# Dual_linear_VCA_chip.net
KiCad netlist of a schematic drawn in EAGLE
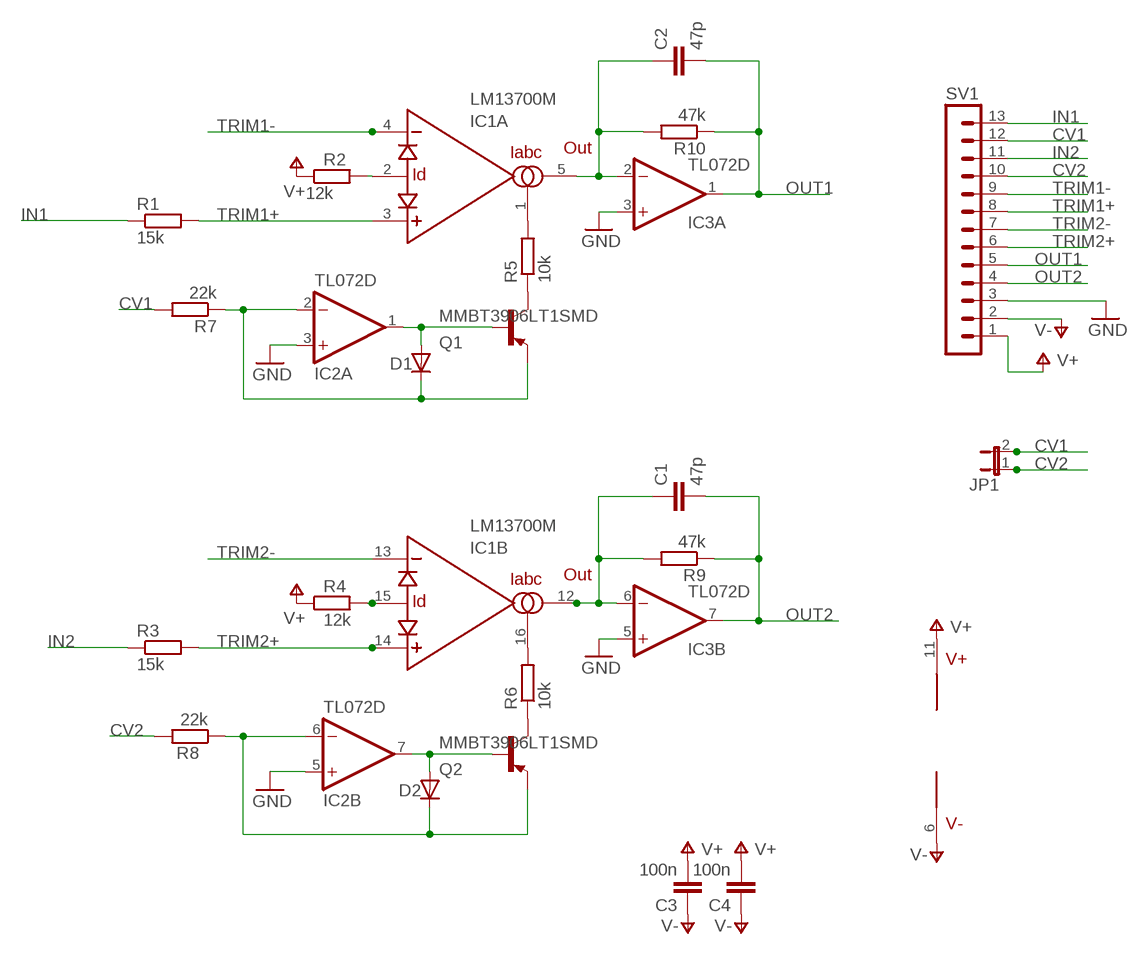
[diagram p0: schematic, sheet 1]

(export (version "E")
  (design (tool "Eeschema 10.0.6"))
  (components
    (comp (ref "C1")
      (value "47p")
      (footprint "eagle-import:C0805")
      (libsource (lib "eagle-import") (part "C-EUC0805"))
    )
    (comp (ref "C2")
      (value "47p")
      (footprint "eagle-import:C0805")
      (libsource (lib "eagle-import") (part "C-EUC0805"))
    )
    (comp (ref "C3")
      (value "100n")
      (footprint "eagle-import:C0805")
      (libsource (lib "eagle-import") (part "C-EUC0805"))
    )
    (comp (ref "C4")
      (value "100n")
      (footprint "eagle-import:C0805")
      (libsource (lib "eagle-import") (part "C-EUC0805"))
    )
    (comp (ref "D1")
      (value "DIODE-SOD80C")
      (footprint "eagle-import:SOD80C")
      (libsource (lib "eagle-import") (part "DIODE-SOD80C"))
    )
    (comp (ref "D2")
      (value "DIODE-SOD80C")
      (footprint "eagle-import:SOD80C")
      (libsource (lib "eagle-import") (part "DIODE-SOD80C"))
    )
    (comp (ref "IC1")
      (value "LM13700M")
      (footprint "eagle-import:SO16")
      (libsource (lib "eagle-import") (part "LM13700M"))
    )
    (comp (ref "IC2")
      (value "TL072D")
      (footprint "eagle-import:SO08")
      (libsource (lib "eagle-import") (part "TL072D"))
    )
    (comp (ref "IC3")
      (value "TL072D")
      (footprint "eagle-import:SO08")
      (libsource (lib "eagle-import") (part "TL072D"))
    )
    (comp (ref "JP1")
      (value "JP1E")
      (footprint "eagle-import:JP1")
      (libsource (lib "eagle-import") (part "JP1E"))
    )
    (comp (ref "Q1")
      (value "MMBT3906LT1SMD")
      (footprint "eagle-import:SOT23-BEC")
      (libsource (lib "eagle-import") (part "MMBT3906SMDLT1"))
    )
    (comp (ref "Q2")
      (value "MMBT3906LT1SMD")
      (footprint "eagle-import:SOT23-BEC")
      (libsource (lib "eagle-import") (part "MMBT3906SMDLT1"))
    )
    (comp (ref "R1")
      (value "15k")
      (footprint "eagle-import:R0805")
      (libsource (lib "eagle-import") (part "R-EU_R0805"))
    )
    (comp (ref "R2")
      (value "12k")
      (footprint "eagle-import:R0805")
      (libsource (lib "eagle-import") (part "R-EU_R0805"))
    )
    (comp (ref "R3")
      (value "15k")
      (footprint "eagle-import:R0805")
      (libsource (lib "eagle-import") (part "R-EU_R0805"))
    )
    (comp (ref "R4")
      (value "12k")
      (footprint "eagle-import:R0805")
      (libsource (lib "eagle-import") (part "R-EU_R0805"))
    )
    (comp (ref "R5")
      (value "10k")
      (footprint "eagle-import:R0805")
      (libsource (lib "eagle-import") (part "R-EU_R0805"))
    )
    (comp (ref "R6")
      (value "10k")
      (footprint "eagle-import:R0805")
      (libsource (lib "eagle-import") (part "R-EU_R0805"))
    )
    (comp (ref "R7")
      (value "22k")
      (footprint "eagle-import:R0805")
      (libsource (lib "eagle-import") (part "R-EU_R0805"))
    )
    (comp (ref "R8")
      (value "22k")
      (footprint "eagle-import:R0805")
      (libsource (lib "eagle-import") (part "R-EU_R0805"))
    )
    (comp (ref "R9")
      (value "47k")
      (footprint "eagle-import:R0805")
      (libsource (lib "eagle-import") (part "R-EU_R0805"))
    )
    (comp (ref "R10")
      (value "47k")
      (footprint "eagle-import:R0805")
      (libsource (lib "eagle-import") (part "R-EU_R0805"))
    )
    (comp (ref "SV1")
      (value "MA13-1")
      (footprint "eagle-import:MA13-1")
      (libsource (lib "eagle-import") (part "MA13-1"))
    )
  )
  (nets
    (net (code "1") (name "/CV1") (class "Default")
      (node (ref "JP1") (pin "2") (pinfunction "2_2") (pintype "passive"))
      (node (ref "R7") (pin "2") (pinfunction "2_2") (pintype "passive"))
      (node (ref "SV1") (pin "12") (pinfunction "12_12") (pintype "passive"))
    )
    (net (code "2") (name "/CV2") (class "Default")
      (node (ref "JP1") (pin "1") (pinfunction "1_1") (pintype "passive"))
      (node (ref "R8") (pin "2") (pinfunction "2_2") (pintype "passive"))
      (node (ref "SV1") (pin "10") (pinfunction "10_10") (pintype "passive"))
    )
    (net (code "3") (name "/IN1") (class "Default")
      (node (ref "R1") (pin "1") (pinfunction "1_1") (pintype "passive"))
      (node (ref "SV1") (pin "13") (pinfunction "13_13") (pintype "passive"))
    )
    (net (code "4") (name "/IN2") (class "Default")
      (node (ref "R3") (pin "1") (pinfunction "1_1") (pintype "passive"))
      (node (ref "SV1") (pin "11") (pinfunction "11_11") (pintype "passive"))
    )
    (net (code "5") (name "/OUT1") (class "Default")
      (node (ref "C2") (pin "2") (pinfunction "2_2") (pintype "passive"))
      (node (ref "IC3") (pin "1") (pinfunction "OUT_1") (pintype "output"))
      (node (ref "R10") (pin "1") (pinfunction "1_1") (pintype "passive"))
      (node (ref "SV1") (pin "4") (pinfunction "4_4") (pintype "passive"))
    )
    (net (code "6") (name "/OUT2") (class "Default")
      (node (ref "C1") (pin "2") (pinfunction "2_2") (pintype "passive"))
      (node (ref "IC3") (pin "7") (pinfunction "OUT_7") (pintype "output"))
      (node (ref "R9") (pin "1") (pinfunction "1_1") (pintype "passive"))
      (node (ref "SV1") (pin "5") (pinfunction "5_5") (pintype "passive"))
    )
    (net (code "7") (name "/TRIM1+") (class "Default")
      (node (ref "IC1") (pin "3") (pinfunction "+IN_3") (pintype "bidirectional"))
      (node (ref "R1") (pin "2") (pinfunction "2_2") (pintype "passive"))
      (node (ref "SV1") (pin "8") (pinfunction "8_8") (pintype "passive"))
    )
    (net (code "8") (name "/TRIM1-") (class "Default")
      (node (ref "IC1") (pin "4") (pinfunction "-IN_4") (pintype "bidirectional"))
      (node (ref "SV1") (pin "9") (pinfunction "9_9") (pintype "passive"))
    )
    (net (code "9") (name "/TRIM2+") (class "Default")
      (node (ref "IC1") (pin "14") (pinfunction "+IN_14") (pintype "bidirectional"))
      (node (ref "R3") (pin "2") (pinfunction "2_2") (pintype "passive"))
      (node (ref "SV1") (pin "6") (pinfunction "6_6") (pintype "passive"))
    )
    (net (code "10") (name "/TRIM2-") (class "Default")
      (node (ref "IC1") (pin "13") (pinfunction "-IN_13") (pintype "bidirectional"))
      (node (ref "SV1") (pin "7") (pinfunction "7_7") (pintype "passive"))
    )
    (net (code "11") (name "GND") (class "Default")
      (node (ref "IC2") (pin "3") (pinfunction "+IN_3") (pintype "input"))
      (node (ref "IC2") (pin "5") (pinfunction "+IN_5") (pintype "input"))
      (node (ref "IC3") (pin "3") (pinfunction "+IN_3") (pintype "input"))
      (node (ref "IC3") (pin "5") (pinfunction "+IN_5") (pintype "input"))
      (node (ref "SV1") (pin "3") (pinfunction "3_3") (pintype "passive"))
    )
    (net (code "12") (name "Net-(IC1A-IABC)") (class "Default")
      (node (ref "IC1") (pin "1") (pinfunction "IABC_1") (pintype "bidirectional"))
      (node (ref "R5") (pin "2") (pinfunction "2_2") (pintype "passive"))
    )
    (net (code "13") (name "Net-(IC1A-ID)") (class "Default")
      (node (ref "IC1") (pin "2") (pinfunction "ID_2") (pintype "bidirectional"))
      (node (ref "R2") (pin "2") (pinfunction "2_2") (pintype "passive"))
    )
    (net (code "14") (name "Net-(IC1A-OUT)") (class "Default")
      (node (ref "C2") (pin "1") (pinfunction "1_1") (pintype "passive"))
      (node (ref "IC1") (pin "5") (pinfunction "OUT_5") (pintype "bidirectional"))
      (node (ref "IC3") (pin "2") (pinfunction "-IN_2") (pintype "input"))
      (node (ref "R10") (pin "2") (pinfunction "2_2") (pintype "passive"))
    )
    (net (code "15") (name "Net-(IC1B-IABC)") (class "Default")
      (node (ref "IC1") (pin "16") (pinfunction "IABC_16") (pintype "bidirectional"))
      (node (ref "R6") (pin "2") (pinfunction "2_2") (pintype "passive"))
    )
    (net (code "16") (name "Net-(IC1B-ID)") (class "Default")
      (node (ref "IC1") (pin "15") (pinfunction "ID_15") (pintype "bidirectional"))
      (node (ref "R4") (pin "2") (pinfunction "2_2") (pintype "passive"))
    )
    (net (code "17") (name "Net-(IC1B-OUT)") (class "Default")
      (node (ref "C1") (pin "1") (pinfunction "1_1") (pintype "passive"))
      (node (ref "IC1") (pin "12") (pinfunction "OUT_12") (pintype "bidirectional"))
      (node (ref "IC3") (pin "6") (pinfunction "-IN_6") (pintype "input"))
      (node (ref "R9") (pin "2") (pinfunction "2_2") (pintype "passive"))
    )
    (net (code "18") (name "Net-(IC2A--IN)") (class "Default")
      (node (ref "D1") (pin "C") (pinfunction "C_C") (pintype "passive"))
      (node (ref "IC2") (pin "2") (pinfunction "-IN_2") (pintype "input"))
      (node (ref "Q1") (pin "E") (pinfunction "E_E") (pintype "passive"))
      (node (ref "R7") (pin "1") (pinfunction "1_1") (pintype "passive"))
    )
    (net (code "19") (name "Net-(IC2A-OUT)") (class "Default")
      (node (ref "D1") (pin "A") (pinfunction "A_A") (pintype "passive"))
      (node (ref "IC2") (pin "1") (pinfunction "OUT_1") (pintype "output"))
      (node (ref "Q1") (pin "B") (pinfunction "B_B") (pintype "passive"))
    )
    (net (code "20") (name "Net-(IC2B--IN)") (class "Default")
      (node (ref "D2") (pin "C") (pinfunction "C_C") (pintype "passive"))
      (node (ref "IC2") (pin "6") (pinfunction "-IN_6") (pintype "input"))
      (node (ref "Q2") (pin "E") (pinfunction "E_E") (pintype "passive"))
      (node (ref "R8") (pin "1") (pinfunction "1_1") (pintype "passive"))
    )
    (net (code "21") (name "Net-(IC2B-OUT)") (class "Default")
      (node (ref "D2") (pin "A") (pinfunction "A_A") (pintype "passive"))
      (node (ref "IC2") (pin "7") (pinfunction "OUT_7") (pintype "output"))
      (node (ref "Q2") (pin "B") (pinfunction "B_B") (pintype "passive"))
    )
    (net (code "22") (name "Net-(Q1-PadC)") (class "Default")
      (node (ref "Q1") (pin "C") (pinfunction "C_C") (pintype "passive"))
      (node (ref "R5") (pin "1") (pinfunction "1_1") (pintype "passive"))
    )
    (net (code "23") (name "Net-(Q2-PadC)") (class "Default")
      (node (ref "Q2") (pin "C") (pinfunction "C_C") (pintype "passive"))
      (node (ref "R6") (pin "1") (pinfunction "1_1") (pintype "passive"))
    )
    (net (code "24") (name "V+") (class "Default")
      (node (ref "C3") (pin "2") (pinfunction "2_2") (pintype "passive"))
      (node (ref "C4") (pin "2") (pinfunction "2_2") (pintype "passive"))
      (node (ref "IC1") (pin "11") (pinfunction "V+_11") (pintype "bidirectional"))
      (node (ref "R2") (pin "1") (pinfunction "1_1") (pintype "passive"))
      (node (ref "R4") (pin "1") (pinfunction "1_1") (pintype "passive"))
      (node (ref "SV1") (pin "1") (pinfunction "1_1") (pintype "passive"))
    )
    (net (code "25") (name "V-") (class "Default")
      (node (ref "C3") (pin "1") (pinfunction "1_1") (pintype "passive"))
      (node (ref "C4") (pin "1") (pinfunction "1_1") (pintype "passive"))
      (node (ref "IC1") (pin "6") (pinfunction "V-_6") (pintype "bidirectional"))
      (node (ref "SV1") (pin "2") (pinfunction "2_2") (pintype "passive"))
    )
  )
)
